# BigButton.net
KiCad netlist of a schematic drawn in EAGLE
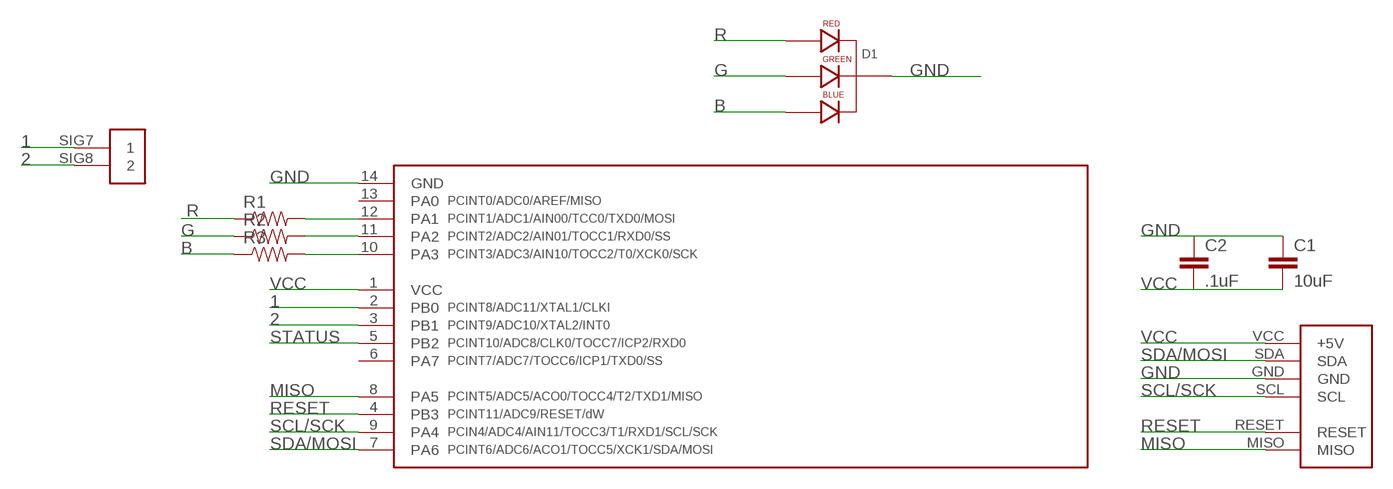
[diagram p0: schematic, sheet 1]

(export (version "E")
  (design (tool "Eeschema 10.0.6"))
  (components
    (comp (ref "C1")
      (value "10uF")
      (footprint "eagle-import:0805")
      (libsource (lib "eagle-import") (part "CAP0805"))
    )
    (comp (ref "C2")
      (value ".1uF")
      (footprint "eagle-import:0805")
      (libsource (lib "eagle-import") (part "CAP0805"))
    )
    (comp (ref "D1")
      (value "LED-RGB-CC-THRUCLEAR")
      (footprint "eagle-import:LED-RGB-THRU")
      (libsource (lib "eagle-import") (part "LED-RGB-CC-THRUCLEAR"))
    )
    (comp (ref "R1")
      (value "RESISTOR0805-RES")
      (footprint "eagle-import:0805")
      (libsource (lib "eagle-import") (part "RESISTOR0805-RES"))
    )
    (comp (ref "R2")
      (value "RESISTOR0805-RES")
      (footprint "eagle-import:0805")
      (libsource (lib "eagle-import") (part "RESISTOR0805-RES"))
    )
    (comp (ref "R3")
      (value "RESISTOR0805-RES")
      (footprint "eagle-import:0805")
      (libsource (lib "eagle-import") (part "RESISTOR0805-RES"))
    )
    (comp (ref "U$1")
      (value "BUTTONPAD")
      (footprint "eagle-import:BUTTONPAD")
      (libsource (lib "eagle-import") (part "BUTTONPAD"))
    )
    (comp (ref "U$3")
      (value "TINY841")
      (footprint "eagle-import:SOIC14")
      (libsource (lib "eagle-import") (part "TINY841"))
    )
    (comp (ref "U$4")
      (value "FOOTPRINTFOOTPRINT-2")
      (footprint "eagle-import:FOOTPRINT2")
      (libsource (lib "eagle-import") (part "FOOTPRINTFOOTPRINT-2"))
    )
  )
  (nets
    (net (code "1") (name "/1") (class "Default")
      (node (ref "U$1") (pin "SIG7") (pinfunction "1_SIG7") (pintype "bidirectional"))
      (node (ref "U$3") (pin "2") (pinfunction "PB0_2") (pintype "bidirectional"))
    )
    (net (code "2") (name "/2") (class "Default")
      (node (ref "U$1") (pin "SIG8") (pinfunction "2_SIG8") (pintype "bidirectional"))
      (node (ref "U$3") (pin "3") (pinfunction "PB1_3") (pintype "bidirectional"))
    )
    (net (code "3") (name "/B") (class "Default")
      (node (ref "D1") (pin "4") (pinfunction "BLUE_CATHODE_4") (pintype "bidirectional"))
      (node (ref "R3") (pin "1") (pinfunction "1_1") (pintype "passive"))
    )
    (net (code "4") (name "/G") (class "Default")
      (node (ref "D1") (pin "3") (pinfunction "GREEN_CATHODE_3") (pintype "bidirectional"))
      (node (ref "R2") (pin "1") (pinfunction "1_1") (pintype "passive"))
    )
    (net (code "5") (name "/GND") (class "Default")
      (node (ref "C1") (pin "1") (pinfunction "1_1") (pintype "passive"))
      (node (ref "C2") (pin "1") (pinfunction "1_1") (pintype "passive"))
      (node (ref "D1") (pin "2") (pinfunction "CATHODE_2") (pintype "bidirectional"))
      (node (ref "U$3") (pin "14") (pinfunction "GND_14") (pintype "bidirectional"))
      (node (ref "U$4") (pin "GND") (pinfunction "GND_GND") (pintype "power_in"))
    )
    (net (code "6") (name "/MISO") (class "Default")
      (node (ref "U$3") (pin "8") (pinfunction "PA5_8") (pintype "bidirectional"))
      (node (ref "U$4") (pin "MISO") (pinfunction "MISO_MISO") (pintype "bidirectional"))
    )
    (net (code "7") (name "/R") (class "Default")
      (node (ref "D1") (pin "1") (pinfunction "RED_CATHODE_1") (pintype "bidirectional"))
      (node (ref "R1") (pin "1") (pinfunction "1_1") (pintype "passive"))
    )
    (net (code "8") (name "/RESET") (class "Default")
      (node (ref "U$3") (pin "4") (pinfunction "PB3_4") (pintype "bidirectional"))
      (node (ref "U$4") (pin "RESET") (pinfunction "RESET_RESET") (pintype "bidirectional"))
    )
    (net (code "9") (name "/SCL{slash}SCK") (class "Default")
      (node (ref "U$3") (pin "9") (pinfunction "PA4_9") (pintype "bidirectional"))
      (node (ref "U$4") (pin "SCL") (pinfunction "SCL_SCL") (pintype "bidirectional"))
    )
    (net (code "10") (name "/SDA{slash}MOSI") (class "Default")
      (node (ref "U$3") (pin "7") (pinfunction "PA6_7") (pintype "bidirectional"))
      (node (ref "U$4") (pin "SDA") (pinfunction "SDA_SDA") (pintype "bidirectional"))
    )
    (net (code "11") (name "/STATUS") (class "Default")
      (node (ref "U$3") (pin "5") (pinfunction "PB2_5") (pintype "bidirectional"))
    )
    (net (code "12") (name "/VCC") (class "Default")
      (node (ref "C1") (pin "2") (pinfunction "2_2") (pintype "passive"))
      (node (ref "C2") (pin "2") (pinfunction "2_2") (pintype "passive"))
      (node (ref "U$3") (pin "1") (pinfunction "VCC_1") (pintype "bidirectional"))
      (node (ref "U$4") (pin "VCC") (pinfunction "+5V_VCC") (pintype "power_in"))
    )
    (net (code "13") (name "Net-(U$3-PA1)") (class "Default")
      (node (ref "R1") (pin "2") (pinfunction "2_2") (pintype "passive"))
      (node (ref "U$3") (pin "12") (pinfunction "PA1_12") (pintype "bidirectional"))
    )
    (net (code "14") (name "Net-(U$3-PA2)") (class "Default")
      (node (ref "R2") (pin "2") (pinfunction "2_2") (pintype "passive"))
      (node (ref "U$3") (pin "11") (pinfunction "PA2_11") (pintype "bidirectional"))
    )
    (net (code "15") (name "Net-(U$3-PA3)") (class "Default")
      (node (ref "R3") (pin "2") (pinfunction "2_2") (pintype "passive"))
      (node (ref "U$3") (pin "10") (pinfunction "PA3_10") (pintype "bidirectional"))
    )
    (net (code "16") (name "unconnected-(U$3-PA0-Pad13)") (class "Default")
      (node (ref "U$3") (pin "13") (pinfunction "PA0_13") (pintype "bidirectional"))
    )
    (net (code "17") (name "unconnected-(U$3-PA7-Pad6)") (class "Default")
      (node (ref "U$3") (pin "6") (pinfunction "PA7_6") (pintype "bidirectional"))
    )
  )
)
